# Oscilador.net
KiCad netlist of a schematic drawn in Altium Designer
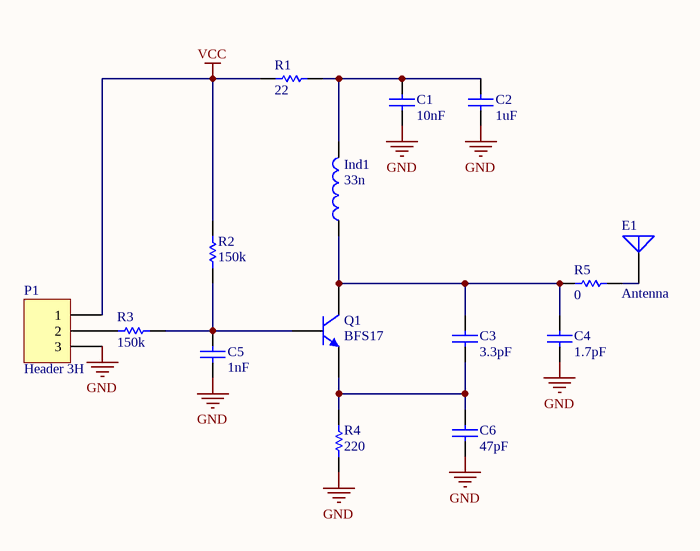
[diagram p0: Oscilador.SchDoc]

(export (version "E")
  (design (tool "Eeschema 10.0.6"))
  (components
    (comp (ref "C1")
      (value "10nF")
      (footprint "0805_CAP")
      (fields (field (name "Comment") "Capacitor"))
      (libsource (lib "epf") (part "Cap"))
    )
    (comp (ref "C2")
      (value "1uF")
      (footprint "0805_CAP")
      (fields (field (name "Comment") "Capacitor"))
      (libsource (lib "epf") (part "Cap"))
    )
    (comp (ref "C3")
      (value "3.3pF")
      (footprint "0805_CAP")
      (fields (field (name "Comment") "Capacitor"))
      (libsource (lib "epf") (part "Cap"))
    )
    (comp (ref "C4")
      (value "1.7pF")
      (footprint "0805_CAP")
      (fields (field (name "Comment") "Capacitor"))
      (libsource (lib "epf") (part "Cap"))
    )
    (comp (ref "C5")
      (value "1nF")
      (footprint "0805_CAP")
      (fields (field (name "Comment") "Capacitor"))
      (libsource (lib "epf") (part "Cap"))
    )
    (comp (ref "C6")
      (value "47pF")
      (footprint "0805_CAP")
      (fields (field (name "Comment") "Capacitor"))
      (libsource (lib "epf") (part "Cap"))
    )
    (comp (ref "E1")
      (value "Antenna")
      (footprint "PIN1")
      (description "Generic Antenna")
      (fields (field (name "PUBLISHER") "Altium Limited"))
      (libsource (lib "Miscellaneous Devices") (part "Antenna"))
    )
    (comp (ref "Ind1")
      (value "Ind2")
      (footprint "RES0603")
      (fields (field (name "VALOR") "33n"))
      (libsource (lib "epf") (part "Ind2"))
    )
    (comp (ref "P1")
      (value "Header 3H")
      (footprint "HDR1X3H")
      (description "Header, 3-Pin, Right Angle")
      (fields (field (name "PUBLISHER") "Altium Limited"))
      (libsource (lib "Miscellaneous Connectors") (part "Header 3H"))
    )
    (comp (ref "Q1")
      (value "BFS17")
      (footprint "SOT23")
      (description "NPN 1 GHz Wideband Transistor")
      (fields (field (name "PUBLISHER") "Altium Limited"))
      (libsource (lib "epf") (part "BFS17"))
    )
    (comp (ref "R1")
      (value "22")
      (footprint "0805_RES")
      (fields (field (name "Comment") "Resistor"))
      (libsource (lib "epf") (part "Res"))
    )
    (comp (ref "R2")
      (value "150k")
      (footprint "0805_RES")
      (fields (field (name "Comment") "Resistor"))
      (libsource (lib "epf") (part "Res"))
    )
    (comp (ref "R3")
      (value "150k")
      (footprint "0805_RES")
      (fields (field (name "Comment") "Resistor"))
      (libsource (lib "epf") (part "Res"))
    )
    (comp (ref "R4")
      (value "220")
      (footprint "0805_RES")
      (fields (field (name "Comment") "Resistor"))
      (libsource (lib "epf") (part "Res"))
    )
    (comp (ref "R5")
      (value "0")
      (footprint "0805_RES")
      (fields (field (name "Comment") "Resistor"))
      (libsource (lib "epf") (part "Res"))
    )
  )
  (nets
    (net (code "1") (name "GND") (class "Default")
      (node (ref "C1") (pin "1") (pinfunction "1_1") (pintype "passive"))
      (node (ref "C2") (pin "1") (pinfunction "1_1") (pintype "passive"))
      (node (ref "C4") (pin "1") (pinfunction "1_1") (pintype "passive"))
      (node (ref "C5") (pin "1") (pinfunction "1_1") (pintype "passive"))
      (node (ref "C6") (pin "1") (pinfunction "1_1") (pintype "passive"))
      (node (ref "P1") (pin "3") (pinfunction "3_3") (pintype "passive"))
      (node (ref "R4") (pin "2") (pinfunction "2_2") (pintype "passive"))
    )
    (net (code "2") (name "Net-(C1-Pad2)") (class "Default")
      (node (ref "C1") (pin "2") (pinfunction "2_2") (pintype "passive"))
      (node (ref "C2") (pin "2") (pinfunction "2_2") (pintype "passive"))
      (node (ref "Ind1") (pin "2") (pinfunction "2_2") (pintype "passive"))
      (node (ref "R1") (pin "2") (pinfunction "2_2") (pintype "passive"))
    )
    (net (code "3") (name "Net-(E1-A)") (class "Default")
      (node (ref "E1") (pin "1") (pinfunction "A_1") (pintype "passive"))
      (node (ref "R5") (pin "2") (pinfunction "2_2") (pintype "passive"))
    )
    (net (code "4") (name "Net-(P1-Pad2)") (class "Default")
      (node (ref "P1") (pin "2") (pinfunction "2_2") (pintype "passive"))
      (node (ref "R3") (pin "1") (pinfunction "1_1") (pintype "passive"))
    )
    (net (code "5") (name "Net-(Q1-B)") (class "Default")
      (node (ref "C5") (pin "2") (pinfunction "2_2") (pintype "passive"))
      (node (ref "Q1") (pin "1") (pinfunction "B_1") (pintype "passive"))
      (node (ref "R2") (pin "2") (pinfunction "2_2") (pintype "passive"))
      (node (ref "R3") (pin "2") (pinfunction "2_2") (pintype "passive"))
    )
    (net (code "6") (name "Net-(Q1-C)") (class "Default")
      (node (ref "C3") (pin "2") (pinfunction "2_2") (pintype "passive"))
      (node (ref "C4") (pin "2") (pinfunction "2_2") (pintype "passive"))
      (node (ref "Ind1") (pin "1") (pinfunction "1_1") (pintype "passive"))
      (node (ref "Q1") (pin "3") (pinfunction "C_3") (pintype "passive"))
      (node (ref "R5") (pin "1") (pinfunction "1_1") (pintype "passive"))
    )
    (net (code "7") (name "Net-(Q1-E)") (class "Default")
      (node (ref "C3") (pin "1") (pinfunction "1_1") (pintype "passive"))
      (node (ref "C6") (pin "2") (pinfunction "2_2") (pintype "passive"))
      (node (ref "Q1") (pin "2") (pinfunction "E_2") (pintype "passive"))
      (node (ref "R4") (pin "1") (pinfunction "1_1") (pintype "passive"))
    )
    (net (code "8") (name "VCC") (class "Default")
      (node (ref "P1") (pin "1") (pinfunction "1_1") (pintype "passive"))
      (node (ref "R1") (pin "1") (pinfunction "1_1") (pintype "passive"))
      (node (ref "R2") (pin "1") (pinfunction "1_1") (pintype "passive"))
    )
  )
)
